# Main.net
KiCad netlist of a schematic drawn in Altium Designer
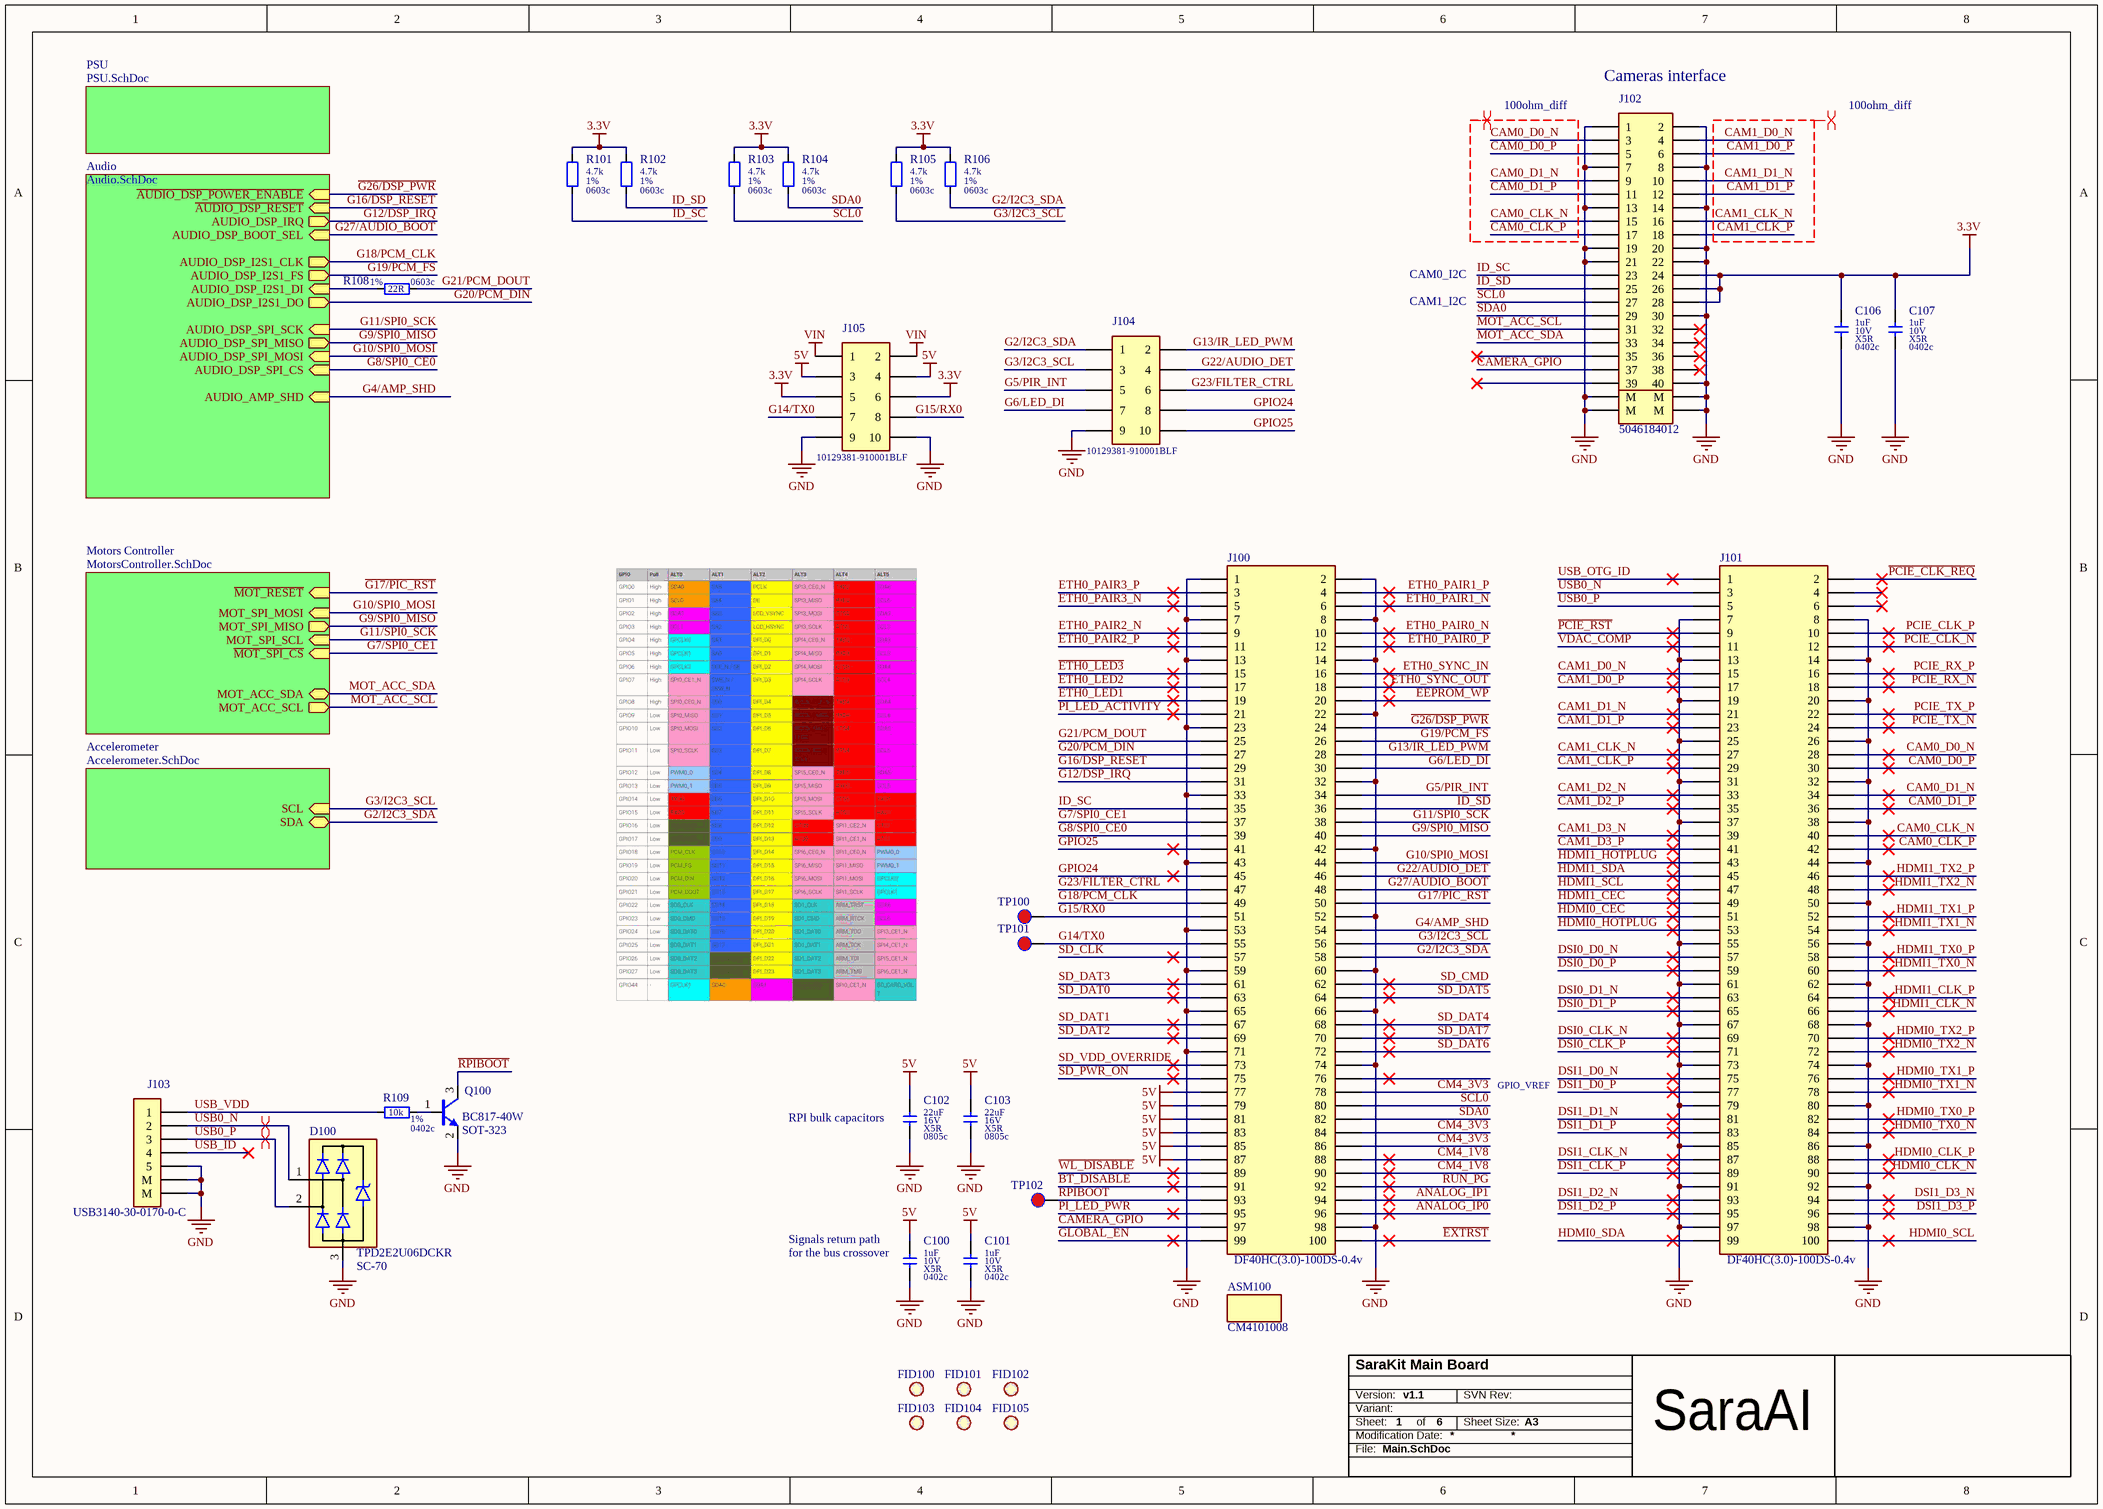
[diagram p0: Main.SchDoc]

(export (version "E")
  (design (tool "Eeschema 10.0.6"))
  (components
    (comp (ref "ASM100")
      (value "CM4101008")
      (footprint "RASPBERRY PI CM4 EMMC")
      (description "FAS SoM 1GB 8GB")
      (fields (field (name "02 MPN") "CM4101008"))
      (libsource (lib "MS_Altium_Lib") (part "DUMMY BOM"))
    )
    (comp (ref "C100")
      (value "CL05A105KP5NNNC")
      (footprint "CAPC1005X60L")
      (description "SMT 0402c 1uF 10V 10% X5R 10.2MHz 85'C")
      (fields
        (field (name "11 PARAMETER 4") "X5R")
        (field (name "07 PACKAGE") "0402c")
        (field (name "08 PARAMETER 1") "1uF")
        (field (name "09 PARAMETER 2") "10V")
      )
      (libsource (lib "MS_Altium_Lib") (part "CAPACITOR"))
    )
    (comp (ref "C101")
      (value "CL05A105KP5NNNC")
      (footprint "CAPC1005X60L")
      (description "SMT 0402c 1uF 10V 10% X5R 10.2MHz 85'C")
      (fields
        (field (name "11 PARAMETER 4") "X5R")
        (field (name "07 PACKAGE") "0402c")
        (field (name "08 PARAMETER 1") "1uF")
        (field (name "09 PARAMETER 2") "10V")
      )
      (libsource (lib "MS_Altium_Lib") (part "CAPACITOR"))
    )
    (comp (ref "C102")
      (value "CL21A226MOQNNNE")
      (footprint "CAPC2013X145L")
      (description "SMT 0805c 22uF 16V 20% X5R 1.6MHz 85'C")
      (fields
        (field (name "11 PARAMETER 4") "X5R")
        (field (name "07 PACKAGE") "0805c")
        (field (name "08 PARAMETER 1") "22uF")
        (field (name "09 PARAMETER 2") "16V")
      )
      (libsource (lib "MS_Altium_Lib") (part "CAPACITOR"))
    )
    (comp (ref "C103")
      (value "CL21A226MOQNNNE")
      (footprint "CAPC2013X145L")
      (description "SMT 0805c 22uF 16V 20% X5R 1.6MHz 85'C")
      (fields
        (field (name "11 PARAMETER 4") "X5R")
        (field (name "07 PACKAGE") "0805c")
        (field (name "08 PARAMETER 1") "22uF")
        (field (name "09 PARAMETER 2") "16V")
      )
      (libsource (lib "MS_Altium_Lib") (part "CAPACITOR"))
    )
    (comp (ref "C106")
      (value "CL05A105KP5NNNC")
      (footprint "CAPC1005X60L")
      (description "SMT 0402c 1uF 10V 10% X5R 10.2MHz 85'C")
      (fields
        (field (name "11 PARAMETER 4") "X5R")
        (field (name "07 PACKAGE") "0402c")
        (field (name "08 PARAMETER 1") "1uF")
        (field (name "09 PARAMETER 2") "10V")
      )
      (libsource (lib "MS_Altium_Lib") (part "CAPACITOR"))
    )
    (comp (ref "C107")
      (value "CL05A105KP5NNNC")
      (footprint "CAPC1005X60L")
      (description "SMT 0402c 1uF 10V 10% X5R 10.2MHz 85'C")
      (fields
        (field (name "11 PARAMETER 4") "X5R")
        (field (name "07 PACKAGE") "0402c")
        (field (name "08 PARAMETER 1") "1uF")
        (field (name "09 PARAMETER 2") "10V")
      )
      (libsource (lib "MS_Altium_Lib") (part "CAPACITOR"))
    )
    (comp (ref "D100")
      (value "TPD2E2U06DCKR")
      (footprint "SOT65P210X110-3L")
      (description "SMT SC-70 6.5V 5.5A 85W Bidirectional 12.4V 10nA")
      (fields (field (name "02 MPN") "TPD2E2U06DCKR") (field (name "07 PACKAGE") "SC-70"))
      (libsource (lib "MS_Altium_Lib") (part "ESD PEOTECTION DOUBLE"))
    )
    (comp (ref "FID100")
      (value "FIDUCIAL")
      (footprint "FIDUCIAL 2MM")
      (libsource (lib "MS_Altium_Lib") (part "FIDUCIAL"))
    )
    (comp (ref "FID101")
      (value "FIDUCIAL")
      (footprint "FIDUCIAL 2MM")
      (libsource (lib "MS_Altium_Lib") (part "FIDUCIAL"))
    )
    (comp (ref "FID102")
      (value "FIDUCIAL")
      (footprint "FIDUCIAL 2MM")
      (libsource (lib "MS_Altium_Lib") (part "FIDUCIAL"))
    )
    (comp (ref "FID103")
      (value "FIDUCIAL")
      (footprint "FIDUCIAL 2MM")
      (libsource (lib "MS_Altium_Lib") (part "FIDUCIAL"))
    )
    (comp (ref "FID104")
      (value "FIDUCIAL")
      (footprint "FIDUCIAL 2MM")
      (libsource (lib "MS_Altium_Lib") (part "FIDUCIAL"))
    )
    (comp (ref "FID105")
      (value "FIDUCIAL")
      (footprint "FIDUCIAL 2MM")
      (libsource (lib "MS_Altium_Lib") (part "FIDUCIAL"))
    )
    (comp (ref "J100")
      (value "DF40HC(3.0)-100DS-0.4v")
      (footprint "DF40HC(3.0)-100DS-0.4V")
      (description "SMT 2x50 0.4mm Female Straight")
      (fields (field (name "02 MPN") "DF40HC(3.0)-100DS-0.4v"))
      (libsource (lib "MS_Altium_Lib") (part "CONNECTOR 2X50 ODDEVEN"))
    )
    (comp (ref "J101")
      (value "DF40HC(3.0)-100DS-0.4v")
      (footprint "DF40HC(3.0)-100DS-0.4V")
      (description "SMT 2x50 0.4mm Female Straight")
      (fields (field (name "02 MPN") "DF40HC(3.0)-100DS-0.4v"))
      (libsource (lib "MS_Altium_Lib") (part "CONNECTOR 2X50 ODDEVEN"))
    )
    (comp (ref "J102")
      (value "5046184012")
      (footprint "MOLEX 5046184012")
      (description "SMT 2x20 0.35mm Straight 50V 0.3A")
      (fields (field (name "02 MPN") "5046184012"))
      (libsource (lib "MS_Altium_Lib") (part "CONNECTOR 2X22 4MNT ODDEVEN"))
    )
    (comp (ref "J103")
      (value "USB3140-30-0170-0-C")
      (footprint "USB3140-30-0170-0-C")
      (description "SMD/THT USB 0.65mm Straight 30V 1A")
      (fields (field (name "02 MPN") "USB3140-30-0170-0-C"))
      (libsource (lib "MS_Altium_Lib") (part "CONNECTOR 1X5 2MNT"))
    )
    (comp (ref "J104")
      (value "10129381-910001BLF")
      (footprint "Goldpin 2.54 2x5")
      (description "THT 2X5 2.54mm Straight 110V 3A")
      (fields (field (name "02 MPN") "10129381-910001BLF"))
      (libsource (lib "MS_Altium_Lib") (part "CONNECTOR 2X5"))
    )
    (comp (ref "J105")
      (value "10129381-910001BLF")
      (footprint "Goldpin 2.54 2x5")
      (description "THT 2X5 2.54mm Straight 110V 3A")
      (fields (field (name "02 MPN") "10129381-910001BLF"))
      (libsource (lib "MS_Altium_Lib") (part "CONNECTOR 2X5"))
    )
    (comp (ref "Q100")
      (value "BC817-40W")
      (footprint "SOT65P210X110-3L")
      (description "SMT SOT-323 NPN 45V 0.5A 0.2W")
      (fields (field (name "02 MPN") "BC817-40W") (field (name "07 PACKAGE") "SOT-323"))
      (libsource (lib "MS_Altium_Lib") (part "TRANSISTOR NPN 1B 2E 3C"))
    )
    (comp (ref "R101")
      (value "RC0603FR-074K7L")
      (footprint "RESC1608X55L")
      (description "SMT 0603c 4.7k 1% 100mW 100ppm/K 75V")
      (fields
        (field (name "07 PACKAGE") "0603c")
        (field (name "09 PARAMETER 2") "1%")
        (field (name "08 PARAMETER 1") "4.7k")
      )
      (libsource (lib "") (part "RESISTOR_1"))
    )
    (comp (ref "R102")
      (value "RC0603FR-074K7L")
      (footprint "RESC1608X55L")
      (description "SMT 0603c 4.7k 1% 100mW 100ppm/K 75V")
      (fields
        (field (name "07 PACKAGE") "0603c")
        (field (name "09 PARAMETER 2") "1%")
        (field (name "08 PARAMETER 1") "4.7k")
      )
      (libsource (lib "") (part "RESISTOR_1"))
    )
    (comp (ref "R103")
      (value "RC0603FR-074K7L")
      (footprint "RESC1608X55L")
      (description "SMT 0603c 4.7k 1% 100mW 100ppm/K 75V")
      (fields
        (field (name "07 PACKAGE") "0603c")
        (field (name "09 PARAMETER 2") "1%")
        (field (name "08 PARAMETER 1") "4.7k")
      )
      (libsource (lib "") (part "RESISTOR_1"))
    )
    (comp (ref "R104")
      (value "RC0603FR-074K7L")
      (footprint "RESC1608X55L")
      (description "SMT 0603c 4.7k 1% 100mW 100ppm/K 75V")
      (fields
        (field (name "07 PACKAGE") "0603c")
        (field (name "09 PARAMETER 2") "1%")
        (field (name "08 PARAMETER 1") "4.7k")
      )
      (libsource (lib "") (part "RESISTOR_1"))
    )
    (comp (ref "R105")
      (value "RC0603FR-074K7L")
      (footprint "RESC1608X55L")
      (description "SMT 0603c 4.7k 1% 100mW 100ppm/K 75V")
      (fields
        (field (name "07 PACKAGE") "0603c")
        (field (name "09 PARAMETER 2") "1%")
        (field (name "08 PARAMETER 1") "4.7k")
      )
      (libsource (lib "") (part "RESISTOR_1"))
    )
    (comp (ref "R106")
      (value "RC0603FR-074K7L")
      (footprint "RESC1608X55L")
      (description "SMT 0603c 4.7k 1% 100mW 100ppm/K 75V")
      (fields
        (field (name "07 PACKAGE") "0603c")
        (field (name "09 PARAMETER 2") "1%")
        (field (name "08 PARAMETER 1") "4.7k")
      )
      (libsource (lib "") (part "RESISTOR_1"))
    )
    (comp (ref "R108")
      (value "RC0603FR-0722RL")
      (footprint "RESC1608X55L")
      (description "SMT 0603c 22R 1% 100mW 100ppm/K 75V")
      (fields
        (field (name "07 PACKAGE") "0603c")
        (field (name "09 PARAMETER 2") "1%")
        (field (name "08 PARAMETER 1") "22R")
      )
      (libsource (lib "") (part "RESISTOR_2"))
    )
    (comp (ref "R109")
      (value "RC0402FR-0710KL")
      (footprint "RESC1005X40L")
      (description "SMT 0402c 10k 1% 62.5mW 100ppm/K 50V")
      (fields
        (field (name "07 PACKAGE") "0402c")
        (field (name "09 PARAMETER 2") "1%")
        (field (name "08 PARAMETER 1") "10k")
      )
      (libsource (lib "MS_Altium_Lib") (part "RESISTOR"))
    )
    (comp (ref "TP100")
      (value "TESTPAD")
      (footprint "TP 1.2mm")
      (libsource (lib "MS_Altium_Lib") (part "TESTPAD"))
    )
    (comp (ref "TP101")
      (value "TESTPAD")
      (footprint "TP 1.2mm")
      (libsource (lib "MS_Altium_Lib") (part "TESTPAD"))
    )
    (comp (ref "TP102")
      (value "TESTPAD")
      (footprint "TP 1.2mm")
      (libsource (lib "MS_Altium_Lib") (part "TESTPAD"))
    )
  )
  (nets
    (net (code "1") (name "/ANALOG_IP0") (class "Default")
      (node (ref "J100") (pin "96") (pinfunction "96_96") (pintype "passive"))
    )
    (net (code "2") (name "/ANALOG_IP1") (class "Default")
      (node (ref "J100") (pin "94") (pinfunction "94_94") (pintype "passive"))
    )
    (net (code "3") (name "/AUDIO_DSP_I2S1_DI") (class "Default")
      (node (ref "R108") (pin "1") (pinfunction "1_1") (pintype "passive"))
    )
    (net (code "4") (name "/BT_DISABLE") (class "Default")
      (node (ref "J100") (pin "91") (pinfunction "91_91") (pintype "passive"))
    )
    (net (code "5") (name "/CAM0_CLK_N") (class "Default")
      (node (ref "J101") (pin "40") (pinfunction "40_40") (pintype "passive"))
      (node (ref "J102") (pin "15") (pinfunction "15_15") (pintype "passive"))
    )
    (net (code "6") (name "/CAM0_CLK_P") (class "Default")
      (node (ref "J101") (pin "42") (pinfunction "42_42") (pintype "passive"))
      (node (ref "J102") (pin "17") (pinfunction "17_17") (pintype "passive"))
    )
    (net (code "7") (name "/CAM0_D0_N") (class "Default")
      (node (ref "J101") (pin "28") (pinfunction "28_28") (pintype "passive"))
      (node (ref "J102") (pin "3") (pinfunction "3_3") (pintype "passive"))
    )
    (net (code "8") (name "/CAM0_D0_P") (class "Default")
      (node (ref "J101") (pin "30") (pinfunction "30_30") (pintype "passive"))
      (node (ref "J102") (pin "5") (pinfunction "5_5") (pintype "passive"))
    )
    (net (code "9") (name "/CAM0_D1_N") (class "Default")
      (node (ref "J101") (pin "34") (pinfunction "34_34") (pintype "passive"))
      (node (ref "J102") (pin "9") (pinfunction "9_9") (pintype "passive"))
    )
    (net (code "10") (name "/CAM0_D1_P") (class "Default")
      (node (ref "J101") (pin "36") (pinfunction "36_36") (pintype "passive"))
      (node (ref "J102") (pin "11") (pinfunction "11_11") (pintype "passive"))
    )
    (net (code "11") (name "/CAM1_CLK_N") (class "Default")
      (node (ref "J101") (pin "27") (pinfunction "27_27") (pintype "passive"))
      (node (ref "J102") (pin "16") (pinfunction "16_16") (pintype "passive"))
    )
    (net (code "12") (name "/CAM1_CLK_P") (class "Default")
      (node (ref "J101") (pin "29") (pinfunction "29_29") (pintype "passive"))
      (node (ref "J102") (pin "18") (pinfunction "18_18") (pintype "passive"))
    )
    (net (code "13") (name "/CAM1_D0_N") (class "Default")
      (node (ref "J101") (pin "15") (pinfunction "15_15") (pintype "passive"))
      (node (ref "J102") (pin "4") (pinfunction "4_4") (pintype "passive"))
    )
    (net (code "14") (name "/CAM1_D0_P") (class "Default")
      (node (ref "J101") (pin "17") (pinfunction "17_17") (pintype "passive"))
      (node (ref "J102") (pin "6") (pinfunction "6_6") (pintype "passive"))
    )
    (net (code "15") (name "/CAM1_D1_N") (class "Default")
      (node (ref "J101") (pin "21") (pinfunction "21_21") (pintype "passive"))
      (node (ref "J102") (pin "10") (pinfunction "10_10") (pintype "passive"))
    )
    (net (code "16") (name "/CAM1_D1_P") (class "Default")
      (node (ref "J101") (pin "23") (pinfunction "23_23") (pintype "passive"))
      (node (ref "J102") (pin "12") (pinfunction "12_12") (pintype "passive"))
    )
    (net (code "17") (name "/CAM1_D2_N") (class "Default")
      (node (ref "J101") (pin "33") (pinfunction "33_33") (pintype "passive"))
    )
    (net (code "18") (name "/CAM1_D2_P") (class "Default")
      (node (ref "J101") (pin "35") (pinfunction "35_35") (pintype "passive"))
    )
    (net (code "19") (name "/CAM1_D3_N") (class "Default")
      (node (ref "J101") (pin "39") (pinfunction "39_39") (pintype "passive"))
    )
    (net (code "20") (name "/CAM1_D3_P") (class "Default")
      (node (ref "J101") (pin "41") (pinfunction "41_41") (pintype "passive"))
    )
    (net (code "21") (name "/CAMERA_GPIO") (class "Default")
      (node (ref "J100") (pin "97") (pinfunction "97_97") (pintype "passive"))
      (node (ref "J102") (pin "37") (pinfunction "37_37") (pintype "passive"))
    )
    (net (code "22") (name "/CM4_1V8") (class "Default")
      (node (ref "J100") (pin "88") (pinfunction "88_88") (pintype "passive"))
      (node (ref "J100") (pin "90") (pinfunction "90_90") (pintype "passive"))
    )
    (net (code "23") (name "/CM4_3V3") (class "Default")
      (node (ref "J100") (pin "78") (pinfunction "78_78") (pintype "passive"))
      (node (ref "J100") (pin "84") (pinfunction "84_84") (pintype "passive"))
      (node (ref "J100") (pin "86") (pinfunction "86_86") (pintype "passive"))
    )
    (net (code "24") (name "/DSI0_CLK_N") (class "Default")
      (node (ref "J101") (pin "69") (pinfunction "69_69") (pintype "passive"))
    )
    (net (code "25") (name "/DSI0_CLK_P") (class "Default")
      (node (ref "J101") (pin "71") (pinfunction "71_71") (pintype "passive"))
    )
    (net (code "26") (name "/DSI0_D0_N") (class "Default")
      (node (ref "J101") (pin "57") (pinfunction "57_57") (pintype "passive"))
    )
    (net (code "27") (name "/DSI0_D0_P") (class "Default")
      (node (ref "J101") (pin "59") (pinfunction "59_59") (pintype "passive"))
    )
    (net (code "28") (name "/DSI0_D1_N") (class "Default")
      (node (ref "J101") (pin "63") (pinfunction "63_63") (pintype "passive"))
    )
    (net (code "29") (name "/DSI0_D1_P") (class "Default")
      (node (ref "J101") (pin "65") (pinfunction "65_65") (pintype "passive"))
    )
    (net (code "30") (name "/DSI1_CLK_N") (class "Default")
      (node (ref "J101") (pin "87") (pinfunction "87_87") (pintype "passive"))
    )
    (net (code "31") (name "/DSI1_CLK_P") (class "Default")
      (node (ref "J101") (pin "89") (pinfunction "89_89") (pintype "passive"))
    )
    (net (code "32") (name "/DSI1_D0_N") (class "Default")
      (node (ref "J101") (pin "75") (pinfunction "75_75") (pintype "passive"))
    )
    (net (code "33") (name "/DSI1_D0_P") (class "Default")
      (node (ref "J101") (pin "77") (pinfunction "77_77") (pintype "passive"))
    )
    (net (code "34") (name "/DSI1_D1_N") (class "Default")
      (node (ref "J101") (pin "81") (pinfunction "81_81") (pintype "passive"))
    )
    (net (code "35") (name "/DSI1_D1_P") (class "Default")
      (node (ref "J101") (pin "83") (pinfunction "83_83") (pintype "passive"))
    )
    (net (code "36") (name "/DSI1_D2_N") (class "Default")
      (node (ref "J101") (pin "93") (pinfunction "93_93") (pintype "passive"))
    )
    (net (code "37") (name "/DSI1_D2_P") (class "Default")
      (node (ref "J101") (pin "95") (pinfunction "95_95") (pintype "passive"))
    )
    (net (code "38") (name "/DSI1_D3_N") (class "Default")
      (node (ref "J101") (pin "94") (pinfunction "94_94") (pintype "passive"))
    )
    (net (code "39") (name "/DSI1_D3_P") (class "Default")
      (node (ref "J101") (pin "96") (pinfunction "96_96") (pintype "passive"))
    )
    (net (code "40") (name "/EEPROM_WP") (class "Default")
      (node (ref "J100") (pin "20") (pinfunction "20_20") (pintype "passive"))
    )
    (net (code "41") (name "/ETH0_LED1") (class "Default")
      (node (ref "J100") (pin "19") (pinfunction "19_19") (pintype "passive"))
    )
    (net (code "42") (name "/ETH0_LED2") (class "Default")
      (node (ref "J100") (pin "17") (pinfunction "17_17") (pintype "passive"))
    )
    (net (code "43") (name "/ETH0_LED3") (class "Default")
      (node (ref "J100") (pin "15") (pinfunction "15_15") (pintype "passive"))
    )
    (net (code "44") (name "/ETH0_PAIR0_N") (class "Default")
      (node (ref "J100") (pin "10") (pinfunction "10_10") (pintype "passive"))
    )
    (net (code "45") (name "/ETH0_PAIR0_P") (class "Default")
      (node (ref "J100") (pin "12") (pinfunction "12_12") (pintype "passive"))
    )
    (net (code "46") (name "/ETH0_PAIR1_N") (class "Default")
      (node (ref "J100") (pin "6") (pinfunction "6_6") (pintype "passive"))
    )
    (net (code "47") (name "/ETH0_PAIR1_P") (class "Default")
      (node (ref "J100") (pin "4") (pinfunction "4_4") (pintype "passive"))
    )
    (net (code "48") (name "/ETH0_PAIR2_N") (class "Default")
      (node (ref "J100") (pin "9") (pinfunction "9_9") (pintype "passive"))
    )
    (net (code "49") (name "/ETH0_PAIR2_P") (class "Default")
      (node (ref "J100") (pin "11") (pinfunction "11_11") (pintype "passive"))
    )
    (net (code "50") (name "/ETH0_PAIR3_N") (class "Default")
      (node (ref "J100") (pin "5") (pinfunction "5_5") (pintype "passive"))
    )
    (net (code "51") (name "/ETH0_PAIR3_P") (class "Default")
      (node (ref "J100") (pin "3") (pinfunction "3_3") (pintype "passive"))
    )
    (net (code "52") (name "/ETH0_SYNC_IN") (class "Default")
      (node (ref "J100") (pin "16") (pinfunction "16_16") (pintype "passive"))
    )
    (net (code "53") (name "/ETH0_SYNC_OUT") (class "Default")
      (node (ref "J100") (pin "18") (pinfunction "18_18") (pintype "passive"))
    )
    (net (code "54") (name "/EXTRST") (class "Default")
      (node (ref "J100") (pin "100") (pinfunction "100_100") (pintype "passive"))
    )
    (net (code "55") (name "/G2{slash}I2C3_SDA") (class "Default")
      (node (ref "J100") (pin "58") (pinfunction "58_58") (pintype "passive"))
      (node (ref "J104") (pin "1") (pinfunction "1_1") (pintype "passive"))
      (node (ref "R106") (pin "1") (pinfunction "1_1") (pintype "passive"))
    )
    (net (code "56") (name "/G3{slash}I2C3_SCL") (class "Default")
      (node (ref "J100") (pin "56") (pinfunction "56_56") (pintype "passive"))
      (node (ref "J104") (pin "3") (pinfunction "3_3") (pintype "passive"))
      (node (ref "R105") (pin "1") (pinfunction "1_1") (pintype "passive"))
    )
    (net (code "57") (name "/G4{slash}AMP_SHD") (class "Default")
      (node (ref "J100") (pin "54") (pinfunction "54_54") (pintype "passive"))
    )
    (net (code "58") (name "/G5{slash}PIR_INT") (class "Default")
      (node (ref "J100") (pin "34") (pinfunction "34_34") (pintype "passive"))
      (node (ref "J104") (pin "5") (pinfunction "5_5") (pintype "passive"))
    )
    (net (code "59") (name "/G6{slash}LED_DI") (class "Default")
      (node (ref "J100") (pin "30") (pinfunction "30_30") (pintype "passive"))
      (node (ref "J104") (pin "7") (pinfunction "7_7") (pintype "passive"))
    )
    (net (code "60") (name "/G7{slash}SPI0_CE1") (class "Default")
      (node (ref "J100") (pin "37") (pinfunction "37_37") (pintype "passive"))
    )
    (net (code "61") (name "/G8{slash}SPI0_CE0") (class "Default")
      (node (ref "J100") (pin "39") (pinfunction "39_39") (pintype "passive"))
    )
    (net (code "62") (name "/G9{slash}SPI0_MISO") (class "Default")
      (node (ref "J100") (pin "40") (pinfunction "40_40") (pintype "passive"))
    )
    (net (code "63") (name "/G10{slash}SPI0_MOSI") (class "Default")
      (node (ref "J100") (pin "44") (pinfunction "44_44") (pintype "passive"))
    )
    (net (code "64") (name "/G11{slash}SPI0_SCK") (class "Default")
      (node (ref "J100") (pin "38") (pinfunction "38_38") (pintype "passive"))
    )
    (net (code "65") (name "/G12{slash}DSP_IRQ") (class "Default")
      (node (ref "J100") (pin "31") (pinfunction "31_31") (pintype "passive"))
    )
    (net (code "66") (name "/G13{slash}IR_LED_PWM") (class "Default")
      (node (ref "J100") (pin "28") (pinfunction "28_28") (pintype "passive"))
      (node (ref "J104") (pin "2") (pinfunction "2_2") (pintype "passive"))
    )
    (net (code "67") (name "/G14{slash}TX0") (class "Default")
      (node (ref "J100") (pin "55") (pinfunction "55_55") (pintype "passive"))
      (node (ref "J105") (pin "7") (pinfunction "7_7") (pintype "passive"))
      (node (ref "TP101") (pin "1") (pinfunction "1_1") (pintype "passive"))
    )
    (net (code "68") (name "/G15{slash}RX0") (class "Default")
      (node (ref "J100") (pin "51") (pinfunction "51_51") (pintype "passive"))
      (node (ref "J105") (pin "8") (pinfunction "8_8") (pintype "passive"))
      (node (ref "TP100") (pin "1") (pinfunction "1_1") (pintype "passive"))
    )
    (net (code "69") (name "/G16{slash}DSP_RESET") (class "Default")
      (node (ref "J100") (pin "29") (pinfunction "29_29") (pintype "passive"))
    )
    (net (code "70") (name "/G17{slash}PIC_RST") (class "Default")
      (node (ref "J100") (pin "50") (pinfunction "50_50") (pintype "passive"))
    )
    (net (code "71") (name "/G18{slash}PCM_CLK") (class "Default")
      (node (ref "J100") (pin "49") (pinfunction "49_49") (pintype "passive"))
    )
    (net (code "72") (name "/G19{slash}PCM_FS") (class "Default")
      (node (ref "J100") (pin "26") (pinfunction "26_26") (pintype "passive"))
    )
    (net (code "73") (name "/G20{slash}PCM_DIN") (class "Default")
      (node (ref "J100") (pin "27") (pinfunction "27_27") (pintype "passive"))
    )
    (net (code "74") (name "/G21{slash}PCM_DOUT") (class "Default")
      (node (ref "J100") (pin "25") (pinfunction "25_25") (pintype "passive"))
      (node (ref "R108") (pin "2") (pinfunction "2_2") (pintype "passive"))
    )
    (net (code "75") (name "/G22{slash}AUDIO_DET") (class "Default")
      (node (ref "J100") (pin "46") (pinfunction "46_46") (pintype "passive"))
      (node (ref "J104") (pin "4") (pinfunction "4_4") (pintype "passive"))
    )
    (net (code "76") (name "/G23{slash}FILTER_CTRL") (class "Default")
      (node (ref "J100") (pin "47") (pinfunction "47_47") (pintype "passive"))
      (node (ref "J104") (pin "6") (pinfunction "6_6") (pintype "passive"))
    )
    (net (code "77") (name "/G26{slash}DSP_PWR") (class "Default")
      (node (ref "J100") (pin "24") (pinfunction "24_24") (pintype "passive"))
    )
    (net (code "78") (name "/G27{slash}AUDIO_BOOT") (class "Default")
      (node (ref "J100") (pin "48") (pinfunction "48_48") (pintype "passive"))
    )
    (net (code "79") (name "/GLOBAL_EN") (class "Default")
      (node (ref "J100") (pin "99") (pinfunction "99_99") (pintype "passive"))
    )
    (net (code "80") (name "/GPIO24") (class "Default")
      (node (ref "J100") (pin "45") (pinfunction "45_45") (pintype "passive"))
      (node (ref "J104") (pin "8") (pinfunction "8_8") (pintype "passive"))
    )
    (net (code "81") (name "/GPIO25") (class "Default")
      (node (ref "J100") (pin "41") (pinfunction "41_41") (pintype "passive"))
      (node (ref "J104") (pin "10") (pinfunction "10_10") (pintype "passive"))
    )
    (net (code "82") (name "/HDMI0_CEC") (class "Default")
      (node (ref "J101") (pin "51") (pinfunction "51_51") (pintype "passive"))
    )
    (net (code "83") (name "/HDMI0_CLK_N") (class "Default")
      (node (ref "J101") (pin "90") (pinfunction "90_90") (pintype "passive"))
    )
    (net (code "84") (name "/HDMI0_CLK_P") (class "Default")
      (node (ref "J101") (pin "88") (pinfunction "88_88") (pintype "passive"))
    )
    (net (code "85") (name "/HDMI0_HOTPLUG") (class "Default")
      (node (ref "J101") (pin "53") (pinfunction "53_53") (pintype "passive"))
    )
    (net (code "86") (name "/HDMI0_SCL") (class "Default")
      (node (ref "J101") (pin "100") (pinfunction "100_100") (pintype "passive"))
    )
    (net (code "87") (name "/HDMI0_SDA") (class "Default")
      (node (ref "J101") (pin "99") (pinfunction "99_99") (pintype "passive"))
    )
    (net (code "88") (name "/HDMI0_TX0_N") (class "Default")
      (node (ref "J101") (pin "84") (pinfunction "84_84") (pintype "passive"))
    )
    (net (code "89") (name "/HDMI0_TX0_P") (class "Default")
      (node (ref "J101") (pin "82") (pinfunction "82_82") (pintype "passive"))
    )
    (net (code "90") (name "/HDMI0_TX1_N") (class "Default")
      (node (ref "J101") (pin "78") (pinfunction "78_78") (pintype "passive"))
    )
    (net (code "91") (name "/HDMI0_TX1_P") (class "Default")
      (node (ref "J101") (pin "76") (pinfunction "76_76") (pintype "passive"))
    )
    (net (code "92") (name "/HDMI0_TX2_N") (class "Default")
      (node (ref "J101") (pin "72") (pinfunction "72_72") (pintype "passive"))
    )
    (net (code "93") (name "/HDMI0_TX2_P") (class "Default")
      (node (ref "J101") (pin "70") (pinfunction "70_70") (pintype "passive"))
    )
    (net (code "94") (name "/HDMI1_CEC") (class "Default")
      (node (ref "J101") (pin "49") (pinfunction "49_49") (pintype "passive"))
    )
    (net (code "95") (name "/HDMI1_CLK_N") (class "Default")
      (node (ref "J101") (pin "66") (pinfunction "66_66") (pintype "passive"))
    )
    (net (code "96") (name "/HDMI1_CLK_P") (class "Default")
      (node (ref "J101") (pin "64") (pinfunction "64_64") (pintype "passive"))
    )
    (net (code "97") (name "/HDMI1_HOTPLUG") (class "Default")
      (node (ref "J101") (pin "43") (pinfunction "43_43") (pintype "passive"))
    )
    (net (code "98") (name "/HDMI1_SCL") (class "Default")
      (node (ref "J101") (pin "47") (pinfunction "47_47") (pintype "passive"))
    )
    (net (code "99") (name "/HDMI1_SDA") (class "Default")
      (node (ref "J101") (pin "45") (pinfunction "45_45") (pintype "passive"))
    )
    (net (code "100") (name "/HDMI1_TX0_N") (class "Default")
      (node (ref "J101") (pin "60") (pinfunction "60_60") (pintype "passive"))
    )
    (net (code "101") (name "/HDMI1_TX0_P") (class "Default")
      (node (ref "J101") (pin "58") (pinfunction "58_58") (pintype "passive"))
    )
    (net (code "102") (name "/HDMI1_TX1_N") (class "Default")
      (node (ref "J101") (pin "54") (pinfunction "54_54") (pintype "passive"))
    )
    (net (code "103") (name "/HDMI1_TX1_P") (class "Default")
      (node (ref "J101") (pin "52") (pinfunction "52_52") (pintype "passive"))
    )
    (net (code "104") (name "/HDMI1_TX2_N") (class "Default")
      (node (ref "J101") (pin "48") (pinfunction "48_48") (pintype "passive"))
    )
    (net (code "105") (name "/HDMI1_TX2_P") (class "Default")
      (node (ref "J101") (pin "46") (pinfunction "46_46") (pintype "passive"))
    )
    (net (code "106") (name "/ID_SC") (class "Default")
      (node (ref "J100") (pin "35") (pinfunction "35_35") (pintype "passive"))
      (node (ref "J102") (pin "23") (pinfunction "23_23") (pintype "passive"))
      (node (ref "R101") (pin "1") (pinfunction "1_1") (pintype "passive"))
    )
    (net (code "107") (name "/ID_SD") (class "Default")
      (node (ref "J100") (pin "36") (pinfunction "36_36") (pintype "passive"))
      (node (ref "J102") (pin "25") (pinfunction "25_25") (pintype "passive"))
      (node (ref "R102") (pin "1") (pinfunction "1_1") (pintype "passive"))
    )
    (net (code "108") (name "/MOT_ACC_SCL") (class "Default")
      (node (ref "J102") (pin "31") (pinfunction "31_31") (pintype "passive"))
    )
    (net (code "109") (name "/MOT_ACC_SDA") (class "Default")
      (node (ref "J102") (pin "33") (pinfunction "33_33") (pintype "passive"))
    )
    (net (code "110") (name "/PCIE_CLK_N") (class "Default")
      (node (ref "J101") (pin "12") (pinfunction "12_12") (pintype "passive"))
    )
    (net (code "111") (name "/PCIE_CLK_P") (class "Default")
      (node (ref "J101") (pin "10") (pinfunction "10_10") (pintype "passive"))
    )
    (net (code "112") (name "/PCIE_CLK_REQ") (class "Default")
      (node (ref "J101") (pin "2") (pinfunction "2_2") (pintype "passive"))
    )
    (net (code "113") (name "/PCIE_RST") (class "Default")
      (node (ref "J101") (pin "9") (pinfunction "9_9") (pintype "passive"))
    )
    (net (code "114") (name "/PCIE_RX_N") (class "Default")
      (node (ref "J101") (pin "18") (pinfunction "18_18") (pintype "passive"))
    )
    (net (code "115") (name "/PCIE_RX_P") (class "Default")
      (node (ref "J101") (pin "16") (pinfunction "16_16") (pintype "passive"))
    )
    (net (code "116") (name "/PCIE_TX_N") (class "Default")
      (node (ref "J101") (pin "24") (pinfunction "24_24") (pintype "passive"))
    )
    (net (code "117") (name "/PCIE_TX_P") (class "Default")
      (node (ref "J101") (pin "22") (pinfunction "22_22") (pintype "passive"))
    )
    (net (code "118") (name "/PI_LED_ACTIVITY") (class "Default")
      (node (ref "J100") (pin "21") (pinfunction "21_21") (pintype "passive"))
    )
    (net (code "119") (name "/PI_LED_PWR") (class "Default")
      (node (ref "J100") (pin "95") (pinfunction "95_95") (pintype "passive"))
    )
    (net (code "120") (name "/RPIBOOT") (class "Default")
      (node (ref "J100") (pin "93") (pinfunction "93_93") (pintype "passive"))
      (node (ref "Q100") (pin "3") (pinfunction "C_3") (pintype "passive"))
      (node (ref "TP102") (pin "1") (pinfunction "1_1") (pintype "passive"))
    )
    (net (code "121") (name "/RUN_PG") (class "Default")
      (node (ref "J100") (pin "92") (pinfunction "92_92") (pintype "passive"))
    )
    (net (code "122") (name "/SCL0") (class "Default")
      (node (ref "J100") (pin "80") (pinfunction "80_80") (pintype "passive"))
      (node (ref "J102") (pin "27") (pinfunction "27_27") (pintype "passive"))
      (node (ref "R103") (pin "1") (pinfunction "1_1") (pintype "passive"))
    )
    (net (code "123") (name "/SDA0") (class "Default")
      (node (ref "J100") (pin "82") (pinfunction "82_82") (pintype "passive"))
      (node (ref "J102") (pin "29") (pinfunction "29_29") (pintype "passive"))
      (node (ref "R104") (pin "1") (pinfunction "1_1") (pintype "passive"))
    )
    (net (code "124") (name "/SD_CLK") (class "Default")
      (node (ref "J100") (pin "57") (pinfunction "57_57") (pintype "passive"))
    )
    (net (code "125") (name "/SD_CMD") (class "Default")
      (node (ref "J100") (pin "62") (pinfunction "62_62") (pintype "passive"))
    )
    (net (code "126") (name "/SD_DAT0") (class "Default")
      (node (ref "J100") (pin "63") (pinfunction "63_63") (pintype "passive"))
    )
    (net (code "127") (name "/SD_DAT1") (class "Default")
      (node (ref "J100") (pin "67") (pinfunction "67_67") (pintype "passive"))
    )
    (net (code "128") (name "/SD_DAT2") (class "Default")
      (node (ref "J100") (pin "69") (pinfunction "69_69") (pintype "passive"))
    )
    (net (code "129") (name "/SD_DAT3") (class "Default")
      (node (ref "J100") (pin "61") (pinfunction "61_61") (pintype "passive"))
    )
    (net (code "130") (name "/SD_DAT4") (class "Default")
      (node (ref "J100") (pin "68") (pinfunction "68_68") (pintype "passive"))
    )
    (net (code "131") (name "/SD_DAT5") (class "Default")
      (node (ref "J100") (pin "64") (pinfunction "64_64") (pintype "passive"))
    )
    (net (code "132") (name "/SD_DAT6") (class "Default")
      (node (ref "J100") (pin "72") (pinfunction "72_72") (pintype "passive"))
    )
    (net (code "133") (name "/SD_DAT7") (class "Default")
      (node (ref "J100") (pin "70") (pinfunction "70_70") (pintype "passive"))
    )
    (net (code "134") (name "/SD_PWR_ON") (class "Default")
      (node (ref "J100") (pin "75") (pinfunction "75_75") (pintype "passive"))
    )
    (net (code "135") (name "/SD_VDD_OVERRIDE") (class "Default")
      (node (ref "J100") (pin "73") (pinfunction "73_73") (pintype "passive"))
    )
    (net (code "136") (name "/USB0_N") (class "Default")
      (node (ref "D100") (pin "1") (pinfunction "1_1") (pintype "passive"))
      (node (ref "J101") (pin "3") (pinfunction "3_3") (pintype "passive"))
      (node (ref "J103") (pin "2") (pinfunction "2_2") (pintype "passive"))
    )
    (net (code "137") (name "/USB0_P") (class "Default")
      (node (ref "D100") (pin "2") (pinfunction "2_2") (pintype "passive"))
      (node (ref "J101") (pin "5") (pinfunction "5_5") (pintype "passive"))
      (node (ref "J103") (pin "3") (pinfunction "3_3") (pintype "passive"))
    )
    (net (code "138") (name "/USB_ID") (class "Default")
      (node (ref "J103") (pin "4") (pinfunction "4_4") (pintype "passive+no_connect"))
    )
    (net (code "139") (name "/USB_OTG_ID") (class "Default")
      (node (ref "J101") (pin "1") (pinfunction "1_1") (pintype "passive"))
    )
    (net (code "140") (name "/USB_VDD") (class "Default")
      (node (ref "J103") (pin "1") (pinfunction "1_1") (pintype "passive"))
      (node (ref "R109") (pin "2") (pinfunction "2_2") (pintype "passive"))
    )
    (net (code "141") (name "/VDAC_COMP") (class "Default")
      (node (ref "J101") (pin "11") (pinfunction "11_11") (pintype "passive"))
    )
    (net (code "142") (name "/WL_DISABLE") (class "Default")
      (node (ref "J100") (pin "89") (pinfunction "89_89") (pintype "passive"))
    )
    (net (code "143") (name "3.3V") (class "Default")
      (node (ref "C106") (pin "2") (pinfunction "2_2") (pintype "passive"))
      (node (ref "C107") (pin "2") (pinfunction "2_2") (pintype "passive"))
      (node (ref "J102") (pin "24") (pinfunction "24_24") (pintype "passive"))
      (node (ref "J102") (pin "26") (pinfunction "26_26") (pintype "passive"))
      (node (ref "J102") (pin "28") (pinfunction "28_28") (pintype "passive"))
      (node (ref "J105") (pin "5") (pinfunction "5_5") (pintype "passive"))
      (node (ref "J105") (pin "6") (pinfunction "6_6") (pintype "passive"))
      (node (ref "R101") (pin "2") (pinfunction "2_2") (pintype "passive"))
      (node (ref "R102") (pin "2") (pinfunction "2_2") (pintype "passive"))
      (node (ref "R103") (pin "2") (pinfunction "2_2") (pintype "passive"))
      (node (ref "R104") (pin "2") (pinfunction "2_2") (pintype "passive"))
      (node (ref "R105") (pin "2") (pinfunction "2_2") (pintype "passive"))
      (node (ref "R106") (pin "2") (pinfunction "2_2") (pintype "passive"))
    )
    (net (code "144") (name "5V") (class "Default")
      (node (ref "C100") (pin "2") (pinfunction "2_2") (pintype "passive"))
      (node (ref "C101") (pin "2") (pinfunction "2_2") (pintype "passive"))
      (node (ref "C102") (pin "2") (pinfunction "2_2") (pintype "passive"))
      (node (ref "C103") (pin "2") (pinfunction "2_2") (pintype "passive"))
      (node (ref "J100") (pin "77") (pinfunction "77_77") (pintype "passive"))
      (node (ref "J100") (pin "79") (pinfunction "79_79") (pintype "passive"))
      (node (ref "J100") (pin "81") (pinfunction "81_81") (pintype "passive"))
      (node (ref "J100") (pin "83") (pinfunction "83_83") (pintype "passive"))
      (node (ref "J100") (pin "85") (pinfunction "85_85") (pintype "passive"))
      (node (ref "J100") (pin "87") (pinfunction "87_87") (pintype "passive"))
      (node (ref "J105") (pin "3") (pinfunction "3_3") (pintype "passive"))
      (node (ref "J105") (pin "4") (pinfunction "4_4") (pintype "passive"))
    )
    (net (code "145") (name "GND") (class "Default")
      (node (ref "C100") (pin "1") (pinfunction "1_1") (pintype "passive"))
      (node (ref "C101") (pin "1") (pinfunction "1_1") (pintype "passive"))
      (node (ref "C102") (pin "1") (pinfunction "1_1") (pintype "passive"))
      (node (ref "C103") (pin "1") (pinfunction "1_1") (pintype "passive"))
      (node (ref "C106") (pin "1") (pinfunction "1_1") (pintype "passive"))
      (node (ref "C107") (pin "1") (pinfunction "1_1") (pintype "passive"))
      (node (ref "D100") (pin "3") (pinfunction "3_3") (pintype "passive"))
      (node (ref "J100") (pin "1") (pinfunction "1_1") (pintype "passive"))
      (node (ref "J100") (pin "13") (pinfunction "13_13") (pintype "passive"))
      (node (ref "J100") (pin "14") (pinfunction "14_14") (pintype "passive"))
      (node (ref "J100") (pin "2") (pinfunction "2_2") (pintype "passive"))
      (node (ref "J100") (pin "22") (pinfunction "22_22") (pintype "passive"))
      (node (ref "J100") (pin "23") (pinfunction "23_23") (pintype "passive"))
      (node (ref "J100") (pin "32") (pinfunction "32_32") (pintype "passive"))
      (node (ref "J100") (pin "33") (pinfunction "33_33") (pintype "passive"))
      (node (ref "J100") (pin "42") (pinfunction "42_42") (pintype "passive"))
      (node (ref "J100") (pin "43") (pinfunction "43_43") (pintype "passive"))
      (node (ref "J100") (pin "52") (pinfunction "52_52") (pintype "passive"))
      (node (ref "J100") (pin "53") (pinfunction "53_53") (pintype "passive"))
      (node (ref "J100") (pin "59") (pinfunction "59_59") (pintype "passive"))
      (node (ref "J100") (pin "60") (pinfunction "60_60") (pintype "passive"))
      (node (ref "J100") (pin "65") (pinfunction "65_65") (pintype "passive"))
      (node (ref "J100") (pin "66") (pinfunction "66_66") (pintype "passive"))
      (node (ref "J100") (pin "7") (pinfunction "7_7") (pintype "passive"))
      (node (ref "J100") (pin "71") (pinfunction "71_71") (pintype "passive"))
      (node (ref "J100") (pin "74") (pinfunction "74_74") (pintype "passive"))
      (node (ref "J100") (pin "8") (pinfunction "8_8") (pintype "passive"))
      (node (ref "J100") (pin "98") (pinfunction "98_98") (pintype "passive"))
      (node (ref "J101") (pin "13") (pinfunction "13_13") (pintype "passive"))
      (node (ref "J101") (pin "14") (pinfunction "14_14") (pintype "passive"))
      (node (ref "J101") (pin "19") (pinfunction "19_19") (pintype "passive"))
      (node (ref "J101") (pin "20") (pinfunction "20_20") (pintype "passive"))
      (node (ref "J101") (pin "25") (pinfunction "25_25") (pintype "passive"))
      (node (ref "J101") (pin "26") (pinfunction "26_26") (pintype "passive"))
      (node (ref "J101") (pin "31") (pinfunction "31_31") (pintype "passive"))
      (node (ref "J101") (pin "32") (pinfunction "32_32") (pintype "passive"))
      (node (ref "J101") (pin "37") (pinfunction "37_37") (pintype "passive"))
      (node (ref "J101") (pin "38") (pinfunction "38_38") (pintype "passive"))
      (node (ref "J101") (pin "44") (pinfunction "44_44") (pintype "passive"))
      (node (ref "J101") (pin "50") (pinfunction "50_50") (pintype "passive"))
      (node (ref "J101") (pin "55") (pinfunction "55_55") (pintype "passive"))
      (node (ref "J101") (pin "56") (pinfunction "56_56") (pintype "passive"))
      (node (ref "J101") (pin "61") (pinfunction "61_61") (pintype "passive"))
      (node (ref "J101") (pin "62") (pinfunction "62_62") (pintype "passive"))
      (node (ref "J101") (pin "67") (pinfunction "67_67") (pintype "passive"))
      (node (ref "J101") (pin "68") (pinfunction "68_68") (pintype "passive"))
      (node (ref "J101") (pin "7") (pinfunction "7_7") (pintype "passive"))
      (node (ref "J101") (pin "73") (pinfunction "73_73") (pintype "passive"))
      (node (ref "J101") (pin "74") (pinfunction "74_74") (pintype "passive"))
      (node (ref "J101") (pin "79") (pinfunction "79_79") (pintype "passive"))
      (node (ref "J101") (pin "8") (pinfunction "8_8") (pintype "passive"))
      (node (ref "J101") (pin "80") (pinfunction "80_80") (pintype "passive"))
      (node (ref "J101") (pin "85") (pinfunction "85_85") (pintype "passive"))
      (node (ref "J101") (pin "86") (pinfunction "86_86") (pintype "passive"))
      (node (ref "J101") (pin "91") (pinfunction "91_91") (pintype "passive"))
      (node (ref "J101") (pin "92") (pinfunction "92_92") (pintype "passive"))
      (node (ref "J101") (pin "97") (pinfunction "97_97") (pintype "passive"))
      (node (ref "J101") (pin "98") (pinfunction "98_98") (pintype "passive"))
      (node (ref "J102") (pin "1") (pinfunction "1_1") (pintype "passive"))
      (node (ref "J102") (pin "13") (pinfunction "13_13") (pintype "passive"))
      (node (ref "J102") (pin "14") (pinfunction "14_14") (pintype "passive"))
      (node (ref "J102") (pin "19") (pinfunction "19_19") (pintype "passive"))
      (node (ref "J102") (pin "2") (pinfunction "2_2") (pintype "passive"))
      (node (ref "J102") (pin "20") (pinfunction "20_20") (pintype "passive"))
      (node (ref "J102") (pin "21") (pinfunction "21_21") (pintype "passive"))
      (node (ref "J102") (pin "22") (pinfunction "22_22") (pintype "passive"))
      (node (ref "J102") (pin "30") (pinfunction "30_30") (pintype "passive"))
      (node (ref "J102") (pin "40") (pinfunction "40_40") (pintype "passive"))
      (node (ref "J102") (pin "41") (pinfunction "M_41") (pintype "passive"))
      (node (ref "J102") (pin "42") (pinfunction "M_42") (pintype "passive"))
      (node (ref "J102") (pin "43") (pinfunction "M_43") (pintype "passive"))
      (node (ref "J102") (pin "44") (pinfunction "M_44") (pintype "passive"))
      (node (ref "J102") (pin "7") (pinfunction "7_7") (pintype "passive"))
      (node (ref "J102") (pin "8") (pinfunction "8_8") (pintype "passive"))
      (node (ref "J103") (pin "5") (pinfunction "5_5") (pintype "passive"))
      (node (ref "J103") (pin "MNT1") (pinfunction "M_MNT1") (pintype "passive"))
      (node (ref "J103") (pin "MNT2") (pinfunction "M_MNT2") (pintype "passive"))
      (node (ref "J104") (pin "9") (pinfunction "9_9") (pintype "passive"))
      (node (ref "J105") (pin "10") (pinfunction "10_10") (pintype "passive"))
      (node (ref "J105") (pin "9") (pinfunction "9_9") (pintype "passive"))
      (node (ref "Q100") (pin "2") (pinfunction "E_2") (pintype "passive"))
    )
    (net (code "146") (name "Net-(Q100-B)") (class "Default")
      (node (ref "Q100") (pin "1") (pinfunction "B_1") (pintype "passive"))
      (node (ref "R109") (pin "1") (pinfunction "1_1") (pintype "passive"))
    )
    (net (code "147") (name "VIN") (class "Default")
      (node (ref "J105") (pin "1") (pinfunction "1_1") (pintype "passive"))
      (node (ref "J105") (pin "2") (pinfunction "2_2") (pintype "passive"))
    )
    (net (code "148") (name "unconnected-(J100-Pad76)") (class "Default")
      (node (ref "J100") (pin "76") (pinfunction "76_76") (pintype "passive"))
    )
    (net (code "149") (name "unconnected-(J101-Pad4)") (class "Default")
      (node (ref "J101") (pin "4") (pinfunction "4_4") (pintype "passive+no_connect"))
    )
    (net (code "150") (name "unconnected-(J101-Pad6)") (class "Default")
      (node (ref "J101") (pin "6") (pinfunction "6_6") (pintype "passive+no_connect"))
    )
    (net (code "151") (name "unconnected-(J102-Pad32)") (class "Default")
      (node (ref "J102") (pin "32") (pinfunction "32_32") (pintype "passive+no_connect"))
    )
    (net (code "152") (name "unconnected-(J102-Pad34)") (class "Default")
      (node (ref "J102") (pin "34") (pinfunction "34_34") (pintype "passive+no_connect"))
    )
    (net (code "153") (name "unconnected-(J102-Pad35)") (class "Default")
      (node (ref "J102") (pin "35") (pinfunction "35_35") (pintype "passive+no_connect"))
    )
    (net (code "154") (name "unconnected-(J102-Pad36)") (class "Default")
      (node (ref "J102") (pin "36") (pinfunction "36_36") (pintype "passive+no_connect"))
    )
    (net (code "155") (name "unconnected-(J102-Pad38)") (class "Default")
      (node (ref "J102") (pin "38") (pinfunction "38_38") (pintype "passive+no_connect"))
    )
    (net (code "156") (name "unconnected-(J102-Pad39)") (class "Default")
      (node (ref "J102") (pin "39") (pinfunction "39_39") (pintype "passive+no_connect"))
    )
  )
)
